# ROwen_main.net
KiCad netlist of a schematic drawn in EAGLE
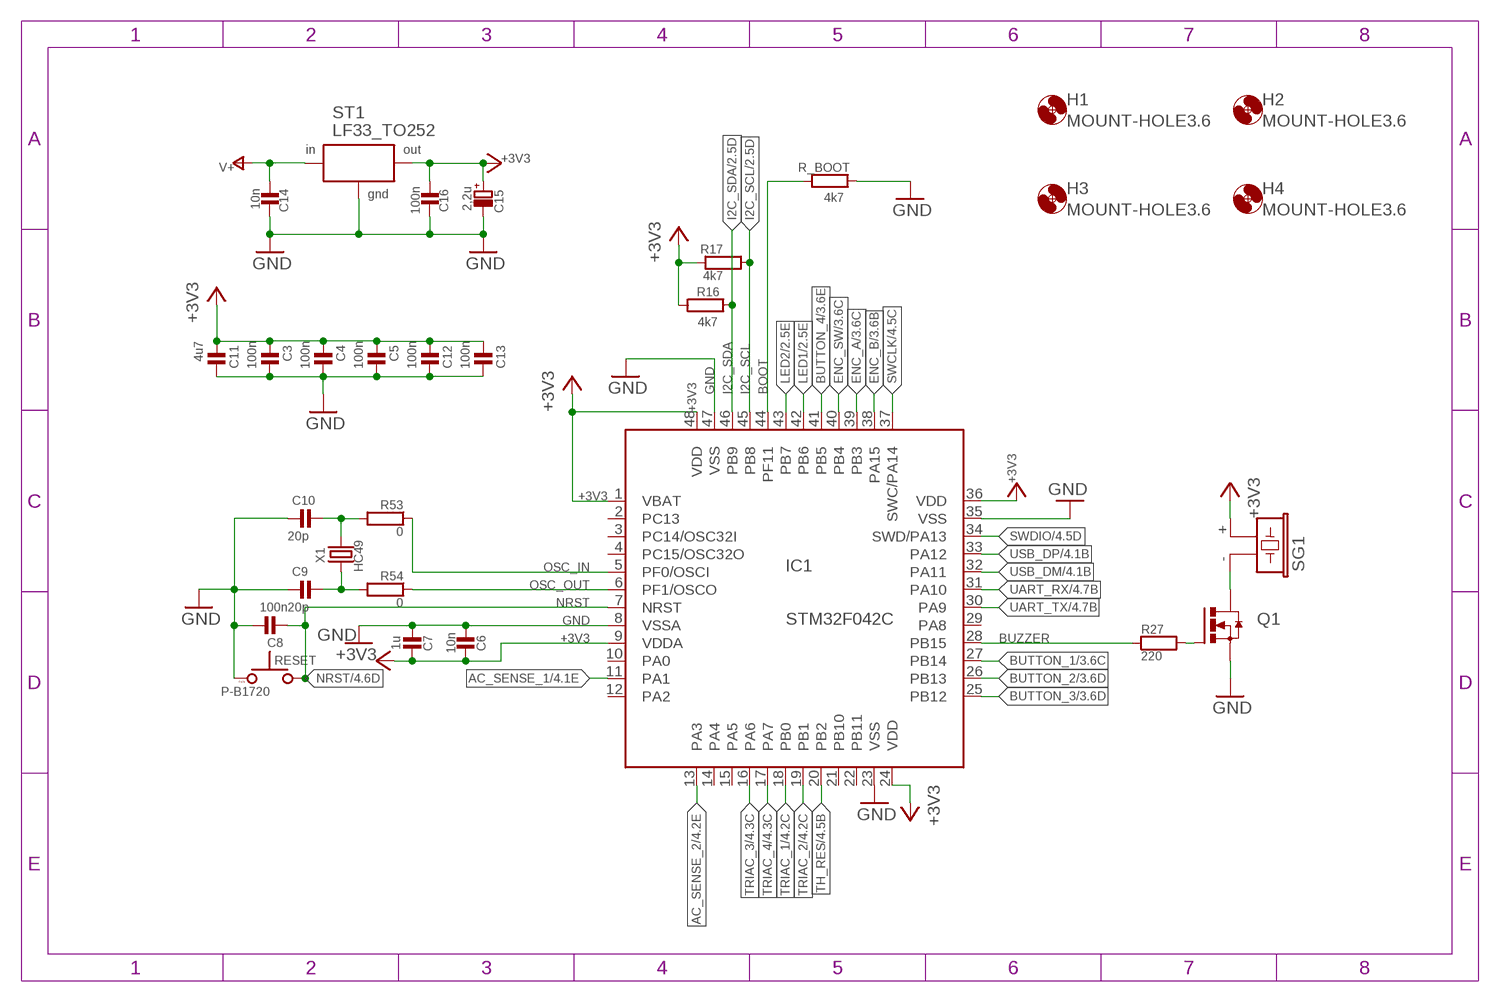
[diagram p0: schematic, sheet 1]
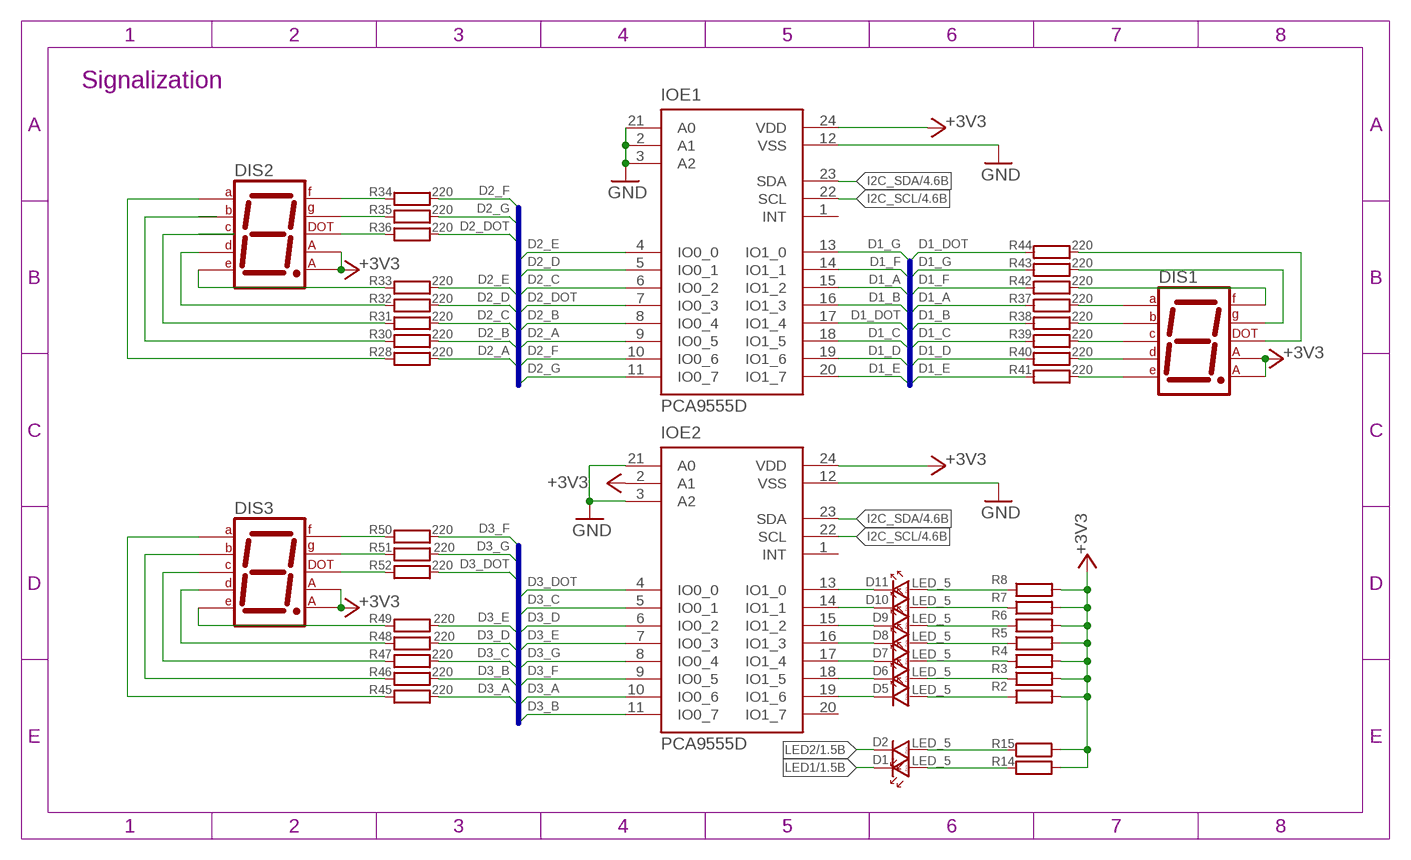
[diagram p1: schematic, sheet 2]
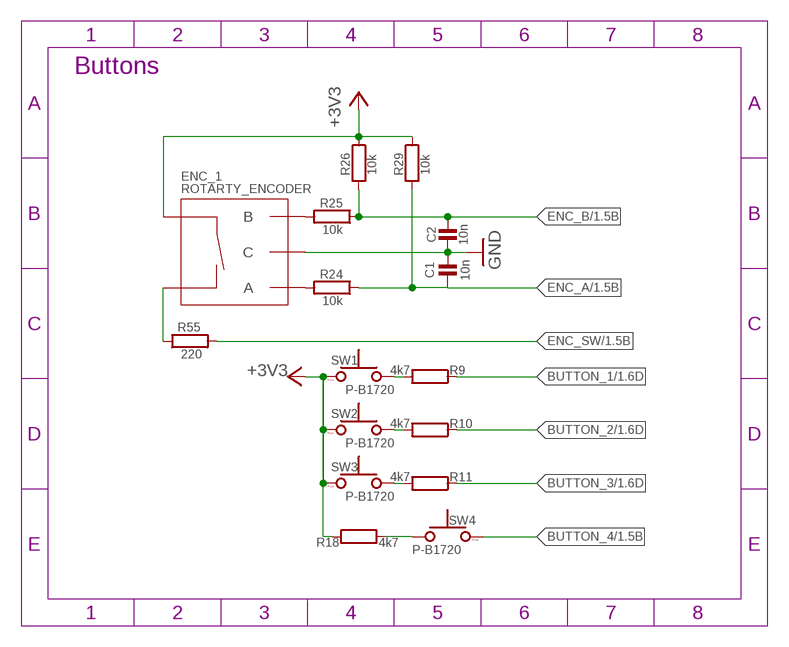
[diagram p2: schematic, sheet 3]
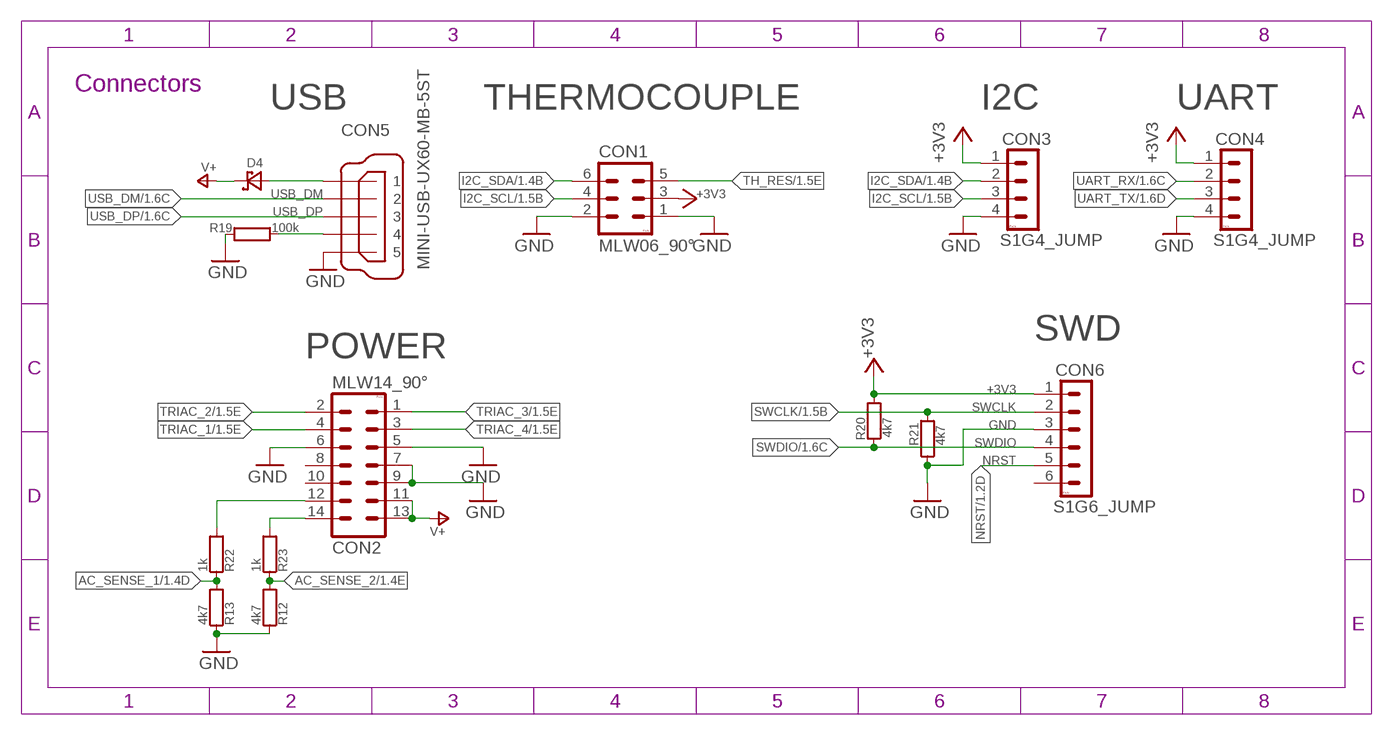
[diagram p3: schematic, sheet 4]

(export (version "E")
  (design (tool "Eeschema 10.0.6"))
  (components
    (comp (ref "C1")
      (value "10n")
      (footprint "eagle-import:0603")
      (libsource (lib "eagle-import") (part "C0603"))
    )
    (comp (ref "C2")
      (value "10n")
      (footprint "eagle-import:0603")
      (libsource (lib "eagle-import") (part "C0603"))
    )
    (comp (ref "ENC_1")
      (value "ROTARTY_ENCODER")
      (footprint "eagle-import:ROTARY_ENC_PLAIN")
      (libsource (lib "eagle-import") (part "ROTARTY_ENCODER"))
    )
    (comp (ref "R9")
      (value "4k7")
      (footprint "eagle-import:0603")
      (libsource (lib "eagle-import") (part "R_R0603"))
    )
    (comp (ref "R10")
      (value "4k7")
      (footprint "eagle-import:0603")
      (libsource (lib "eagle-import") (part "R_R0603"))
    )
    (comp (ref "R11")
      (value "4k7")
      (footprint "eagle-import:0603")
      (libsource (lib "eagle-import") (part "R_R0603"))
    )
    (comp (ref "R18")
      (value "4k7")
      (footprint "eagle-import:0603")
      (libsource (lib "eagle-import") (part "R_R0603"))
    )
    (comp (ref "R24")
      (value "10k")
      (footprint "eagle-import:0603")
      (libsource (lib "eagle-import") (part "R_R0603"))
    )
    (comp (ref "R25")
      (value "10k")
      (footprint "eagle-import:0603")
      (libsource (lib "eagle-import") (part "R_R0603"))
    )
    (comp (ref "R26")
      (value "10k")
      (footprint "eagle-import:0603")
      (libsource (lib "eagle-import") (part "R_R0603"))
    )
    (comp (ref "R29")
      (value "10k")
      (footprint "eagle-import:0603")
      (libsource (lib "eagle-import") (part "R_R0603"))
    )
    (comp (ref "R55")
      (value "220")
      (footprint "eagle-import:0603")
      (libsource (lib "eagle-import") (part "R_R0603"))
    )
    (comp (ref "SW1")
      (value "P-B1720")
      (footprint "eagle-import:P-B1720")
      (libsource (lib "eagle-import") (part "P-B1720"))
    )
    (comp (ref "SW2")
      (value "P-B1720")
      (footprint "eagle-import:P-B1720")
      (libsource (lib "eagle-import") (part "P-B1720"))
    )
    (comp (ref "SW3")
      (value "P-B1720")
      (footprint "eagle-import:P-B1720")
      (libsource (lib "eagle-import") (part "P-B1720"))
    )
    (comp (ref "SW4")
      (value "P-B1720")
      (footprint "eagle-import:P-B1720")
      (libsource (lib "eagle-import") (part "P-B1720"))
    )
    (comp (ref "CON1")
      (value "MLW06_90°")
      (footprint "eagle-import:MLW06A")
      (libsource (lib "eagle-import") (part "MLW06_90°"))
    )
    (comp (ref "CON2")
      (value "MLW14_90°")
      (footprint "eagle-import:MLW14A")
      (libsource (lib "eagle-import") (part "MLW14_90°"))
    )
    (comp (ref "CON3")
      (value "S1G4_JUMP")
      (footprint "eagle-import:S1G4_JUM")
      (libsource (lib "eagle-import") (part "S1G4_JUMP"))
    )
    (comp (ref "CON4")
      (value "S1G4_JUMP")
      (footprint "eagle-import:S1G4_JUM")
      (libsource (lib "eagle-import") (part "S1G4_JUMP"))
    )
    (comp (ref "CON5")
      (value "MINI-USB-UX60-MB-5ST")
      (footprint "eagle-import:UX60-MB-5ST")
      (libsource (lib "eagle-import") (part "MINI-USB-UX60-MB-5ST"))
    )
    (comp (ref "CON6")
      (value "S1G6_JUMP")
      (footprint "eagle-import:S1G6_JUM")
      (libsource (lib "eagle-import") (part "S1G6_JUMP"))
    )
    (comp (ref "D4")
      (value "D_SCHOTKY_SMA")
      (footprint "eagle-import:D_SMA")
      (libsource (lib "eagle-import") (part "D_SCHOTKY_SMA"))
    )
    (comp (ref "R12")
      (value "4k7")
      (footprint "eagle-import:0603")
      (libsource (lib "eagle-import") (part "R_R0603"))
    )
    (comp (ref "R13")
      (value "4k7")
      (footprint "eagle-import:0603")
      (libsource (lib "eagle-import") (part "R_R0603"))
    )
    (comp (ref "R19")
      (value "100k")
      (footprint "eagle-import:0603")
      (libsource (lib "eagle-import") (part "R_R0603"))
    )
    (comp (ref "R20")
      (value "4k7")
      (footprint "eagle-import:0603")
      (libsource (lib "eagle-import") (part "R_R0603"))
    )
    (comp (ref "R21")
      (value "4k7")
      (footprint "eagle-import:0603")
      (libsource (lib "eagle-import") (part "R_R0603"))
    )
    (comp (ref "R22")
      (value "1k")
      (footprint "eagle-import:0603")
      (libsource (lib "eagle-import") (part "R_R0603"))
    )
    (comp (ref "R23")
      (value "1k")
      (footprint "eagle-import:0603")
      (libsource (lib "eagle-import") (part "R_R0603"))
    )
    (comp (ref "C3")
      (value "100n")
      (footprint "eagle-import:0603")
      (libsource (lib "eagle-import") (part "C0603"))
    )
    (comp (ref "C4")
      (value "100n")
      (footprint "eagle-import:0603")
      (libsource (lib "eagle-import") (part "C0603"))
    )
    (comp (ref "C5")
      (value "100n")
      (footprint "eagle-import:0603")
      (libsource (lib "eagle-import") (part "C0603"))
    )
    (comp (ref "C6")
      (value "10n")
      (footprint "eagle-import:0603")
      (libsource (lib "eagle-import") (part "C0603"))
    )
    (comp (ref "C7")
      (value "1u")
      (footprint "eagle-import:0603")
      (libsource (lib "eagle-import") (part "C0603"))
    )
    (comp (ref "C8")
      (value "100n")
      (footprint "eagle-import:0603")
      (libsource (lib "eagle-import") (part "C0603"))
    )
    (comp (ref "C9")
      (value "20p")
      (footprint "eagle-import:0603")
      (libsource (lib "eagle-import") (part "C0603"))
    )
    (comp (ref "C10")
      (value "20p")
      (footprint "eagle-import:0603")
      (libsource (lib "eagle-import") (part "C0603"))
    )
    (comp (ref "C11")
      (value "4u7")
      (footprint "eagle-import:0603")
      (libsource (lib "eagle-import") (part "C0603"))
    )
    (comp (ref "C12")
      (value "100n")
      (footprint "eagle-import:0603")
      (libsource (lib "eagle-import") (part "C0603"))
    )
    (comp (ref "C13")
      (value "100n")
      (footprint "eagle-import:0603")
      (libsource (lib "eagle-import") (part "C0603"))
    )
    (comp (ref "C14")
      (value "10n")
      (footprint "eagle-import:0603")
      (libsource (lib "eagle-import") (part "C0603"))
    )
    (comp (ref "C15")
      (value "2,2u")
      (footprint "eagle-import:ER_08,5_05")
      (libsource (lib "eagle-import") (part "CEE5-8.5"))
    )
    (comp (ref "C16")
      (value "100n")
      (footprint "eagle-import:0603")
      (libsource (lib "eagle-import") (part "C0603"))
    )
    (comp (ref "H1")
      (value "MOUNT-HOLE3.6")
      (footprint "eagle-import:3,6")
      (libsource (lib "eagle-import") (part "MOUNT-HOLE3.6"))
    )
    (comp (ref "H2")
      (value "MOUNT-HOLE3.6")
      (footprint "eagle-import:3,6")
      (libsource (lib "eagle-import") (part "MOUNT-HOLE3.6"))
    )
    (comp (ref "H3")
      (value "MOUNT-HOLE3.6")
      (footprint "eagle-import:3,6")
      (libsource (lib "eagle-import") (part "MOUNT-HOLE3.6"))
    )
    (comp (ref "H4")
      (value "MOUNT-HOLE3.6")
      (footprint "eagle-import:3,6")
      (libsource (lib "eagle-import") (part "MOUNT-HOLE3.6"))
    )
    (comp (ref "IC1")
      (value "STM32F042C")
      (footprint "eagle-import:LQFP48")
      (libsource (lib "eagle-import") (part "STM32F042C"))
    )
    (comp (ref "Q1")
      (value "N-HEXFET-2D_SOT232-IRLL014N")
      (footprint "eagle-import:SOT223")
      (libsource (lib "eagle-import") (part "N-HEXFET-2D_?-SOT232IRLL014N"))
    )
    (comp (ref "R16")
      (value "4k7")
      (footprint "eagle-import:0603")
      (libsource (lib "eagle-import") (part "R_R0603"))
    )
    (comp (ref "R17")
      (value "4k7")
      (footprint "eagle-import:0603")
      (libsource (lib "eagle-import") (part "R_R0603"))
    )
    (comp (ref "R27")
      (value "220")
      (footprint "eagle-import:0603")
      (libsource (lib "eagle-import") (part "R_R0603"))
    )
    (comp (ref "R53")
      (value "0")
      (footprint "eagle-import:0603")
      (libsource (lib "eagle-import") (part "R_R0603"))
    )
    (comp (ref "R54")
      (value "0")
      (footprint "eagle-import:0603")
      (libsource (lib "eagle-import") (part "R_R0603"))
    )
    (comp (ref "RESET")
      (value "P-B1720")
      (footprint "eagle-import:P-B1720")
      (libsource (lib "eagle-import") (part "P-B1720"))
    )
    (comp (ref "R_BOOT")
      (value "4k7")
      (footprint "eagle-import:0603")
      (libsource (lib "eagle-import") (part "R_R0603"))
    )
    (comp (ref "SG1")
      (value "F/CM12P")
      (footprint "eagle-import:F_CM12P")
      (libsource (lib "eagle-import") (part "F/CM12P"))
    )
    (comp (ref "ST1")
      (value "LF33_TO252")
      (footprint "eagle-import:DPACK")
      (fields (field (name "MPN") "LF33CDT-TR"))
      (libsource (lib "eagle-import") (part "LF33_TO252"))
    )
    (comp (ref "X1")
      (value "HC49")
      (footprint "eagle-import:X_HC49_S")
      (libsource (lib "eagle-import") (part "XHC49"))
    )
    (comp (ref "D1")
      (value "LED_5")
      (footprint "eagle-import:LED_5")
      (libsource (lib "eagle-import") (part "LED_5"))
    )
    (comp (ref "D2")
      (value "LED_5")
      (footprint "eagle-import:LED_5")
      (libsource (lib "eagle-import") (part "LED_5"))
    )
    (comp (ref "D5")
      (value "LED_5")
      (footprint "eagle-import:LED_5")
      (libsource (lib "eagle-import") (part "LED_5"))
    )
    (comp (ref "D6")
      (value "LED_5")
      (footprint "eagle-import:LED_5")
      (libsource (lib "eagle-import") (part "LED_5"))
    )
    (comp (ref "D7")
      (value "LED_5")
      (footprint "eagle-import:LED_5")
      (libsource (lib "eagle-import") (part "LED_5"))
    )
    (comp (ref "D8")
      (value "LED_5")
      (footprint "eagle-import:LED_5")
      (libsource (lib "eagle-import") (part "LED_5"))
    )
    (comp (ref "D9")
      (value "LED_5")
      (footprint "eagle-import:LED_5")
      (libsource (lib "eagle-import") (part "LED_5"))
    )
    (comp (ref "D10")
      (value "LED_5")
      (footprint "eagle-import:LED_5")
      (libsource (lib "eagle-import") (part "LED_5"))
    )
    (comp (ref "D11")
      (value "LED_5")
      (footprint "eagle-import:LED_5")
      (libsource (lib "eagle-import") (part "LED_5"))
    )
    (comp (ref "DIS1")
      (value "7-SEGMENT-CA-0.56\"")
      (footprint "eagle-import:7_SEGMENT_0.56_")
      (libsource (lib "eagle-import") (part "7-SEGMENT-CA-0.56{dblquote}"))
    )
    (comp (ref "DIS2")
      (value "7-SEGMENT-CA-0.56\"")
      (footprint "eagle-import:7_SEGMENT_0.56_")
      (libsource (lib "eagle-import") (part "7-SEGMENT-CA-0.56{dblquote}"))
    )
    (comp (ref "DIS3")
      (value "7-SEGMENT-CA-0.56\"")
      (footprint "eagle-import:7_SEGMENT_0.56_")
      (libsource (lib "eagle-import") (part "7-SEGMENT-CA-0.56{dblquote}"))
    )
    (comp (ref "IOE1")
      (value "PCA9555D")
      (footprint "eagle-import:SO24")
      (libsource (lib "eagle-import") (part "PCA9555D"))
    )
    (comp (ref "IOE2")
      (value "PCA9555D")
      (footprint "eagle-import:SO24")
      (libsource (lib "eagle-import") (part "PCA9555D"))
    )
    (comp (ref "R2")
      (value "R_R0603")
      (footprint "eagle-import:0603")
      (libsource (lib "eagle-import") (part "R_R0603"))
    )
    (comp (ref "R3")
      (value "R_R0603")
      (footprint "eagle-import:0603")
      (libsource (lib "eagle-import") (part "R_R0603"))
    )
    (comp (ref "R4")
      (value "R_R0603")
      (footprint "eagle-import:0603")
      (libsource (lib "eagle-import") (part "R_R0603"))
    )
    (comp (ref "R5")
      (value "R_R0603")
      (footprint "eagle-import:0603")
      (libsource (lib "eagle-import") (part "R_R0603"))
    )
    (comp (ref "R6")
      (value "R_R0603")
      (footprint "eagle-import:0603")
      (libsource (lib "eagle-import") (part "R_R0603"))
    )
    (comp (ref "R7")
      (value "R_R0603")
      (footprint "eagle-import:0603")
      (libsource (lib "eagle-import") (part "R_R0603"))
    )
    (comp (ref "R8")
      (value "R_R0603")
      (footprint "eagle-import:0603")
      (libsource (lib "eagle-import") (part "R_R0603"))
    )
    (comp (ref "R14")
      (value "R_R0603")
      (footprint "eagle-import:0603")
      (libsource (lib "eagle-import") (part "R_R0603"))
    )
    (comp (ref "R15")
      (value "R_R0603")
      (footprint "eagle-import:0603")
      (libsource (lib "eagle-import") (part "R_R0603"))
    )
    (comp (ref "R28")
      (value "220")
      (footprint "eagle-import:0603")
      (libsource (lib "eagle-import") (part "R_R0603"))
    )
    (comp (ref "R30")
      (value "220")
      (footprint "eagle-import:0603")
      (libsource (lib "eagle-import") (part "R_R0603"))
    )
    (comp (ref "R31")
      (value "220")
      (footprint "eagle-import:0603")
      (libsource (lib "eagle-import") (part "R_R0603"))
    )
    (comp (ref "R32")
      (value "220")
      (footprint "eagle-import:0603")
      (libsource (lib "eagle-import") (part "R_R0603"))
    )
    (comp (ref "R33")
      (value "220")
      (footprint "eagle-import:0603")
      (libsource (lib "eagle-import") (part "R_R0603"))
    )
    (comp (ref "R34")
      (value "220")
      (footprint "eagle-import:0603")
      (libsource (lib "eagle-import") (part "R_R0603"))
    )
    (comp (ref "R35")
      (value "220")
      (footprint "eagle-import:0603")
      (libsource (lib "eagle-import") (part "R_R0603"))
    )
    (comp (ref "R36")
      (value "220")
      (footprint "eagle-import:0603")
      (libsource (lib "eagle-import") (part "R_R0603"))
    )
    (comp (ref "R37")
      (value "220")
      (footprint "eagle-import:0603")
      (libsource (lib "eagle-import") (part "R_R0603"))
    )
    (comp (ref "R38")
      (value "220")
      (footprint "eagle-import:0603")
      (libsource (lib "eagle-import") (part "R_R0603"))
    )
    (comp (ref "R39")
      (value "220")
      (footprint "eagle-import:0603")
      (libsource (lib "eagle-import") (part "R_R0603"))
    )
    (comp (ref "R40")
      (value "220")
      (footprint "eagle-import:0603")
      (libsource (lib "eagle-import") (part "R_R0603"))
    )
    (comp (ref "R41")
      (value "220")
      (footprint "eagle-import:0603")
      (libsource (lib "eagle-import") (part "R_R0603"))
    )
    (comp (ref "R42")
      (value "220")
      (footprint "eagle-import:0603")
      (libsource (lib "eagle-import") (part "R_R0603"))
    )
    (comp (ref "R43")
      (value "220")
      (footprint "eagle-import:0603")
      (libsource (lib "eagle-import") (part "R_R0603"))
    )
    (comp (ref "R44")
      (value "220")
      (footprint "eagle-import:0603")
      (libsource (lib "eagle-import") (part "R_R0603"))
    )
    (comp (ref "R45")
      (value "220")
      (footprint "eagle-import:0603")
      (libsource (lib "eagle-import") (part "R_R0603"))
    )
    (comp (ref "R46")
      (value "220")
      (footprint "eagle-import:0603")
      (libsource (lib "eagle-import") (part "R_R0603"))
    )
    (comp (ref "R47")
      (value "220")
      (footprint "eagle-import:0603")
      (libsource (lib "eagle-import") (part "R_R0603"))
    )
    (comp (ref "R48")
      (value "220")
      (footprint "eagle-import:0603")
      (libsource (lib "eagle-import") (part "R_R0603"))
    )
    (comp (ref "R49")
      (value "220")
      (footprint "eagle-import:0603")
      (libsource (lib "eagle-import") (part "R_R0603"))
    )
    (comp (ref "R50")
      (value "220")
      (footprint "eagle-import:0603")
      (libsource (lib "eagle-import") (part "R_R0603"))
    )
    (comp (ref "R51")
      (value "220")
      (footprint "eagle-import:0603")
      (libsource (lib "eagle-import") (part "R_R0603"))
    )
    (comp (ref "R52")
      (value "220")
      (footprint "eagle-import:0603")
      (libsource (lib "eagle-import") (part "R_R0603"))
    )
  )
  (nets
    (net (code "1") (name "+3V3") (class "Default")
      (node (ref "C11") (pin "2") (pinfunction "2_2") (pintype "passive"))
      (node (ref "C12") (pin "2") (pinfunction "2_2") (pintype "passive"))
      (node (ref "C13") (pin "2") (pinfunction "2_2") (pintype "passive"))
      (node (ref "C15") (pin "+") (pinfunction "+_+") (pintype "passive"))
      (node (ref "C16") (pin "2") (pinfunction "2_2") (pintype "passive"))
      (node (ref "C3") (pin "2") (pinfunction "2_2") (pintype "passive"))
      (node (ref "C4") (pin "2") (pinfunction "2_2") (pintype "passive"))
      (node (ref "C5") (pin "2") (pinfunction "2_2") (pintype "passive"))
      (node (ref "C6") (pin "1") (pinfunction "1_1") (pintype "passive"))
      (node (ref "C7") (pin "1") (pinfunction "1_1") (pintype "passive"))
      (node (ref "CON1") (pin "3") (pinfunction "3_3") (pintype "passive"))
      (node (ref "CON3") (pin "1") (pinfunction "1_1") (pintype "passive"))
      (node (ref "CON4") (pin "1") (pinfunction "1_1") (pintype "passive"))
      (node (ref "CON6") (pin "1") (pinfunction "1_1") (pintype "passive"))
      (node (ref "DIS1") (pin "3") (pinfunction "CA2_3") (pintype "passive"))
      (node (ref "DIS1") (pin "8") (pinfunction "CA1_8") (pintype "passive"))
      (node (ref "DIS2") (pin "3") (pinfunction "CA2_3") (pintype "passive"))
      (node (ref "DIS2") (pin "8") (pinfunction "CA1_8") (pintype "passive"))
      (node (ref "DIS3") (pin "3") (pinfunction "CA2_3") (pintype "passive"))
      (node (ref "DIS3") (pin "8") (pinfunction "CA1_8") (pintype "passive"))
      (node (ref "ENC_1") (pin "SW+") (pinfunction "SW+_SW+") (pintype "bidirectional"))
      (node (ref "IC1") (pin "1") (pinfunction "VBAT_1") (pintype "passive"))
      (node (ref "IC1") (pin "24") (pinfunction "VDD_24") (pintype "passive"))
      (node (ref "IC1") (pin "36") (pinfunction "VDD_36") (pintype "passive"))
      (node (ref "IC1") (pin "48") (pinfunction "VDD_48") (pintype "passive"))
      (node (ref "IC1") (pin "9") (pinfunction "VDDA_9") (pintype "passive"))
      (node (ref "IOE1") (pin "24") (pinfunction "VDD_24") (pintype "passive"))
      (node (ref "IOE2") (pin "2") (pinfunction "A1_2") (pintype "bidirectional"))
      (node (ref "IOE2") (pin "24") (pinfunction "VDD_24") (pintype "passive"))
      (node (ref "R14") (pin "2") (pinfunction "2_2") (pintype "passive"))
      (node (ref "R15") (pin "2") (pinfunction "2_2") (pintype "passive"))
      (node (ref "R16") (pin "2") (pinfunction "2_2") (pintype "passive"))
      (node (ref "R17") (pin "2") (pinfunction "2_2") (pintype "passive"))
      (node (ref "R18") (pin "1") (pinfunction "1_1") (pintype "passive"))
      (node (ref "R2") (pin "2") (pinfunction "2_2") (pintype "passive"))
      (node (ref "R20") (pin "2") (pinfunction "2_2") (pintype "passive"))
      (node (ref "R26") (pin "1") (pinfunction "1_1") (pintype "passive"))
      (node (ref "R29") (pin "1") (pinfunction "1_1") (pintype "passive"))
      (node (ref "R3") (pin "2") (pinfunction "2_2") (pintype "passive"))
      (node (ref "R4") (pin "2") (pinfunction "2_2") (pintype "passive"))
      (node (ref "R5") (pin "2") (pinfunction "2_2") (pintype "passive"))
      (node (ref "R6") (pin "2") (pinfunction "2_2") (pintype "passive"))
      (node (ref "R7") (pin "2") (pinfunction "2_2") (pintype "passive"))
      (node (ref "R8") (pin "2") (pinfunction "2_2") (pintype "passive"))
      (node (ref "SG1") (pin "+") (pinfunction "1_+") (pintype "passive"))
      (node (ref "ST1") (pin "3") (pinfunction "OUT_3") (pintype "bidirectional"))
      (node (ref "SW1") (pin "1") (pinfunction "1_1") (pintype "passive"))
      (node (ref "SW2") (pin "1") (pinfunction "1_1") (pintype "passive"))
      (node (ref "SW3") (pin "1") (pinfunction "1_1") (pintype "passive"))
    )
    (net (code "2") (name "AC_SENSE_1") (class "Default")
      (node (ref "IC1") (pin "11") (pinfunction "PA1_11") (pintype "passive"))
      (node (ref "R13") (pin "2") (pinfunction "2_2") (pintype "passive"))
      (node (ref "R22") (pin "1") (pinfunction "1_1") (pintype "passive"))
    )
    (net (code "3") (name "AC_SENSE_2") (class "Default")
      (node (ref "IC1") (pin "13") (pinfunction "PA3_13") (pintype "passive"))
      (node (ref "R12") (pin "2") (pinfunction "2_2") (pintype "passive"))
      (node (ref "R23") (pin "1") (pinfunction "1_1") (pintype "passive"))
    )
    (net (code "4") (name "BOOT") (class "Default")
      (node (ref "IC1") (pin "44") (pinfunction "PF11_44") (pintype "passive"))
      (node (ref "R_BOOT") (pin "2") (pinfunction "2_2") (pintype "passive"))
    )
    (net (code "5") (name "BUTTON_1") (class "Default")
      (node (ref "IC1") (pin "27") (pinfunction "PB14_27") (pintype "passive"))
      (node (ref "R9") (pin "1") (pinfunction "1_1") (pintype "passive"))
    )
    (net (code "6") (name "BUTTON_2") (class "Default")
      (node (ref "IC1") (pin "26") (pinfunction "PB13_26") (pintype "passive"))
      (node (ref "R10") (pin "1") (pinfunction "1_1") (pintype "passive"))
    )
    (net (code "7") (name "BUTTON_3") (class "Default")
      (node (ref "IC1") (pin "25") (pinfunction "PB12_25") (pintype "passive"))
      (node (ref "R11") (pin "1") (pinfunction "1_1") (pintype "passive"))
    )
    (net (code "8") (name "BUTTON_4") (class "Default")
      (node (ref "IC1") (pin "41") (pinfunction "PB5_41") (pintype "passive"))
      (node (ref "SW4") (pin "1") (pinfunction "1_1") (pintype "passive"))
    )
    (net (code "9") (name "BUZZER") (class "Default")
      (node (ref "IC1") (pin "28") (pinfunction "PB15_28") (pintype "passive"))
      (node (ref "R27") (pin "1") (pinfunction "1_1") (pintype "passive"))
    )
    (net (code "10") (name "D1_A") (class "Default")
      (node (ref "IOE1") (pin "15") (pinfunction "IO1_2_15") (pintype "bidirectional"))
      (node (ref "R37") (pin "2") (pinfunction "2_2") (pintype "passive"))
    )
    (net (code "11") (name "D1_B") (class "Default")
      (node (ref "IOE1") (pin "16") (pinfunction "IO1_3_16") (pintype "bidirectional"))
      (node (ref "R38") (pin "2") (pinfunction "2_2") (pintype "passive"))
    )
    (net (code "12") (name "D1_C") (class "Default")
      (node (ref "IOE1") (pin "18") (pinfunction "IO1_5_18") (pintype "bidirectional"))
      (node (ref "R39") (pin "2") (pinfunction "2_2") (pintype "passive"))
    )
    (net (code "13") (name "D1_D") (class "Default")
      (node (ref "IOE1") (pin "19") (pinfunction "IO1_6_19") (pintype "bidirectional"))
      (node (ref "R40") (pin "2") (pinfunction "2_2") (pintype "passive"))
    )
    (net (code "14") (name "D1_DOT") (class "Default")
      (node (ref "IOE1") (pin "17") (pinfunction "IO1_4_17") (pintype "bidirectional"))
      (node (ref "R44") (pin "2") (pinfunction "2_2") (pintype "passive"))
    )
    (net (code "15") (name "D1_E") (class "Default")
      (node (ref "IOE1") (pin "20") (pinfunction "IO1_7_20") (pintype "bidirectional"))
      (node (ref "R41") (pin "2") (pinfunction "2_2") (pintype "passive"))
    )
    (net (code "16") (name "D1_F") (class "Default")
      (node (ref "IOE1") (pin "14") (pinfunction "IO1_1_14") (pintype "bidirectional"))
      (node (ref "R42") (pin "2") (pinfunction "2_2") (pintype "passive"))
    )
    (net (code "17") (name "D1_G") (class "Default")
      (node (ref "IOE1") (pin "13") (pinfunction "IO1_0_13") (pintype "bidirectional"))
      (node (ref "R43") (pin "2") (pinfunction "2_2") (pintype "passive"))
    )
    (net (code "18") (name "D2_A") (class "Default")
      (node (ref "IOE1") (pin "9") (pinfunction "IO0_5_9") (pintype "bidirectional"))
      (node (ref "R28") (pin "2") (pinfunction "2_2") (pintype "passive"))
    )
    (net (code "19") (name "D2_B") (class "Default")
      (node (ref "IOE1") (pin "8") (pinfunction "IO0_4_8") (pintype "bidirectional"))
      (node (ref "R30") (pin "2") (pinfunction "2_2") (pintype "passive"))
    )
    (net (code "20") (name "D2_C") (class "Default")
      (node (ref "IOE1") (pin "6") (pinfunction "IO0_2_6") (pintype "bidirectional"))
      (node (ref "R31") (pin "2") (pinfunction "2_2") (pintype "passive"))
    )
    (net (code "21") (name "D2_D") (class "Default")
      (node (ref "IOE1") (pin "5") (pinfunction "IO0_1_5") (pintype "bidirectional"))
      (node (ref "R32") (pin "2") (pinfunction "2_2") (pintype "passive"))
    )
    (net (code "22") (name "D2_DOT") (class "Default")
      (node (ref "IOE1") (pin "7") (pinfunction "IO0_3_7") (pintype "bidirectional"))
      (node (ref "R36") (pin "2") (pinfunction "2_2") (pintype "passive"))
    )
    (net (code "23") (name "D2_E") (class "Default")
      (node (ref "IOE1") (pin "4") (pinfunction "IO0_0_4") (pintype "bidirectional"))
      (node (ref "R33") (pin "2") (pinfunction "2_2") (pintype "passive"))
    )
    (net (code "24") (name "D2_F") (class "Default")
      (node (ref "IOE1") (pin "10") (pinfunction "IO0_6_10") (pintype "bidirectional"))
      (node (ref "R34") (pin "2") (pinfunction "2_2") (pintype "passive"))
    )
    (net (code "25") (name "D2_G") (class "Default")
      (node (ref "IOE1") (pin "11") (pinfunction "IO0_7_11") (pintype "bidirectional"))
      (node (ref "R35") (pin "2") (pinfunction "2_2") (pintype "passive"))
    )
    (net (code "26") (name "D3_A") (class "Default")
      (node (ref "IOE2") (pin "10") (pinfunction "IO0_6_10") (pintype "bidirectional"))
      (node (ref "R45") (pin "2") (pinfunction "2_2") (pintype "passive"))
    )
    (net (code "27") (name "D3_B") (class "Default")
      (node (ref "IOE2") (pin "11") (pinfunction "IO0_7_11") (pintype "bidirectional"))
      (node (ref "R46") (pin "2") (pinfunction "2_2") (pintype "passive"))
    )
    (net (code "28") (name "D3_C") (class "Default")
      (node (ref "IOE2") (pin "5") (pinfunction "IO0_1_5") (pintype "bidirectional"))
      (node (ref "R47") (pin "2") (pinfunction "2_2") (pintype "passive"))
    )
    (net (code "29") (name "D3_D") (class "Default")
      (node (ref "IOE2") (pin "6") (pinfunction "IO0_2_6") (pintype "bidirectional"))
      (node (ref "R48") (pin "2") (pinfunction "2_2") (pintype "passive"))
    )
    (net (code "30") (name "D3_DOT") (class "Default")
      (node (ref "IOE2") (pin "4") (pinfunction "IO0_0_4") (pintype "bidirectional"))
      (node (ref "R52") (pin "2") (pinfunction "2_2") (pintype "passive"))
    )
    (net (code "31") (name "D3_E") (class "Default")
      (node (ref "IOE2") (pin "7") (pinfunction "IO0_3_7") (pintype "bidirectional"))
      (node (ref "R49") (pin "2") (pinfunction "2_2") (pintype "passive"))
    )
    (net (code "32") (name "D3_F") (class "Default")
      (node (ref "IOE2") (pin "9") (pinfunction "IO0_5_9") (pintype "bidirectional"))
      (node (ref "R50") (pin "2") (pinfunction "2_2") (pintype "passive"))
    )
    (net (code "33") (name "D3_G") (class "Default")
      (node (ref "IOE2") (pin "8") (pinfunction "IO0_4_8") (pintype "bidirectional"))
      (node (ref "R51") (pin "2") (pinfunction "2_2") (pintype "passive"))
    )
    (net (code "34") (name "ENC_A") (class "Default")
      (node (ref "C1") (pin "2") (pinfunction "2_2") (pintype "passive"))
      (node (ref "IC1") (pin "39") (pinfunction "PB3_39") (pintype "passive"))
      (node (ref "R24") (pin "1") (pinfunction "1_1") (pintype "passive"))
      (node (ref "R29") (pin "2") (pinfunction "2_2") (pintype "passive"))
    )
    (net (code "35") (name "ENC_B") (class "Default")
      (node (ref "C2") (pin "1") (pinfunction "1_1") (pintype "passive"))
      (node (ref "IC1") (pin "38") (pinfunction "PA15_38") (pintype "passive"))
      (node (ref "R25") (pin "1") (pinfunction "1_1") (pintype "passive"))
      (node (ref "R26") (pin "2") (pinfunction "2_2") (pintype "passive"))
    )
    (net (code "36") (name "ENC_SW") (class "Default")
      (node (ref "IC1") (pin "40") (pinfunction "PB4_40") (pintype "passive"))
      (node (ref "R55") (pin "2") (pinfunction "2_2") (pintype "passive"))
    )
    (net (code "37") (name "GND") (class "Default")
      (node (ref "C1") (pin "1") (pinfunction "1_1") (pintype "passive"))
      (node (ref "C10") (pin "2") (pinfunction "2_2") (pintype "passive"))
      (node (ref "C11") (pin "1") (pinfunction "1_1") (pintype "passive"))
      (node (ref "C12") (pin "1") (pinfunction "1_1") (pintype "passive"))
      (node (ref "C13") (pin "1") (pinfunction "1_1") (pintype "passive"))
      (node (ref "C14") (pin "2") (pinfunction "2_2") (pintype "passive"))
      (node (ref "C15") (pin "-") (pinfunction "-_-") (pintype "passive"))
      (node (ref "C16") (pin "1") (pinfunction "1_1") (pintype "passive"))
      (node (ref "C2") (pin "2") (pinfunction "2_2") (pintype "passive"))
      (node (ref "C3") (pin "1") (pinfunction "1_1") (pintype "passive"))
      (node (ref "C4") (pin "1") (pinfunction "1_1") (pintype "passive"))
      (node (ref "C5") (pin "1") (pinfunction "1_1") (pintype "passive"))
      (node (ref "C6") (pin "2") (pinfunction "2_2") (pintype "passive"))
      (node (ref "C7") (pin "2") (pinfunction "2_2") (pintype "passive"))
      (node (ref "C8") (pin "1") (pinfunction "1_1") (pintype "passive"))
      (node (ref "C9") (pin "2") (pinfunction "2_2") (pintype "passive"))
      (node (ref "CON1") (pin "1") (pinfunction "1_1") (pintype "passive"))
      (node (ref "CON1") (pin "2") (pinfunction "2_2") (pintype "passive"))
      (node (ref "CON2") (pin "5") (pinfunction "5_5") (pintype "passive"))
      (node (ref "CON2") (pin "6") (pinfunction "6_6") (pintype "passive"))
      (node (ref "CON2") (pin "7") (pinfunction "7_7") (pintype "passive"))
      (node (ref "CON2") (pin "9") (pinfunction "9_9") (pintype "passive"))
      (node (ref "CON3") (pin "4") (pinfunction "4_4") (pintype "passive"))
      (node (ref "CON4") (pin "4") (pinfunction "4_4") (pintype "passive"))
      (node (ref "CON5") (pin "5") (pinfunction "5_5") (pintype "input"))
      (node (ref "CON6") (pin "3") (pinfunction "3_3") (pintype "passive"))
      (node (ref "ENC_1") (pin "C") (pinfunction "C_C") (pintype "bidirectional"))
      (node (ref "IC1") (pin "23") (pinfunction "VSS_23") (pintype "passive"))
      (node (ref "IC1") (pin "35") (pinfunction "VSS_35") (pintype "passive"))
      (node (ref "IC1") (pin "47") (pinfunction "VSS_47") (pintype "passive"))
      (node (ref "IC1") (pin "8") (pinfunction "VSSA_8") (pintype "passive"))
      (node (ref "IOE1") (pin "12") (pinfunction "VSS_12") (pintype "passive"))
      (node (ref "IOE1") (pin "2") (pinfunction "A1_2") (pintype "bidirectional"))
      (node (ref "IOE1") (pin "21") (pinfunction "A0_21") (pintype "bidirectional"))
      (node (ref "IOE1") (pin "3") (pinfunction "A2_3") (pintype "bidirectional"))
      (node (ref "IOE2") (pin "12") (pinfunction "VSS_12") (pintype "passive"))
      (node (ref "IOE2") (pin "21") (pinfunction "A0_21") (pintype "bidirectional"))
      (node (ref "IOE2") (pin "3") (pinfunction "A2_3") (pintype "bidirectional"))
      (node (ref "Q1") (pin "3") (pinfunction "S_3") (pintype "passive"))
      (node (ref "R12") (pin "1") (pinfunction "1_1") (pintype "passive"))
      (node (ref "R13") (pin "1") (pinfunction "1_1") (pintype "passive"))
      (node (ref "R19") (pin "1") (pinfunction "1_1") (pintype "passive"))
      (node (ref "R21") (pin "1") (pinfunction "1_1") (pintype "passive"))
      (node (ref "RESET") (pin "1") (pinfunction "1_1") (pintype "passive"))
      (node (ref "R_BOOT") (pin "1") (pinfunction "1_1") (pintype "passive"))
      (node (ref "ST1") (pin "2") (pinfunction "GND_2") (pintype "bidirectional"))
    )
    (net (code "38") (name "I2C_SCL") (class "Default")
      (node (ref "CON1") (pin "4") (pinfunction "4_4") (pintype "passive"))
      (node (ref "CON3") (pin "3") (pinfunction "3_3") (pintype "passive"))
      (node (ref "IC1") (pin "45") (pinfunction "PB8_45") (pintype "passive"))
      (node (ref "IOE1") (pin "22") (pinfunction "SCL_22") (pintype "bidirectional"))
      (node (ref "IOE2") (pin "22") (pinfunction "SCL_22") (pintype "bidirectional"))
      (node (ref "R17") (pin "1") (pinfunction "1_1") (pintype "passive"))
    )
    (net (code "39") (name "I2C_SDA") (class "Default")
      (node (ref "CON1") (pin "6") (pinfunction "6_6") (pintype "passive"))
      (node (ref "CON3") (pin "2") (pinfunction "2_2") (pintype "passive"))
      (node (ref "IC1") (pin "46") (pinfunction "PB9_46") (pintype "passive"))
      (node (ref "IOE1") (pin "23") (pinfunction "SDA_23") (pintype "bidirectional"))
      (node (ref "IOE2") (pin "23") (pinfunction "SDA_23") (pintype "bidirectional"))
      (node (ref "R16") (pin "1") (pinfunction "1_1") (pintype "passive"))
    )
    (net (code "40") (name "LED1") (class "Default")
      (node (ref "D1") (pin "K") (pinfunction "K_K") (pintype "passive"))
      (node (ref "IC1") (pin "42") (pinfunction "PB6_42") (pintype "passive"))
    )
    (net (code "41") (name "LED2") (class "Default")
      (node (ref "D2") (pin "K") (pinfunction "K_K") (pintype "passive"))
      (node (ref "IC1") (pin "43") (pinfunction "PB7_43") (pintype "passive"))
    )
    (net (code "42") (name "NRST") (class "Default")
      (node (ref "C8") (pin "2") (pinfunction "2_2") (pintype "passive"))
      (node (ref "CON6") (pin "5") (pinfunction "5_5") (pintype "passive"))
      (node (ref "IC1") (pin "7") (pinfunction "NRST_7") (pintype "passive"))
      (node (ref "RESET") (pin "2") (pinfunction "2_2") (pintype "passive"))
    )
    (net (code "43") (name "Net-(C9-Pad1)") (class "Default")
      (node (ref "C9") (pin "1") (pinfunction "1_1") (pintype "passive"))
      (node (ref "R54") (pin "2") (pinfunction "2_2") (pintype "passive"))
      (node (ref "X1") (pin "1") (pinfunction "1_1") (pintype "passive"))
    )
    (net (code "44") (name "Net-(C10-Pad1)") (class "Default")
      (node (ref "C10") (pin "1") (pinfunction "1_1") (pintype "passive"))
      (node (ref "R53") (pin "2") (pinfunction "2_2") (pintype "passive"))
      (node (ref "X1") (pin "2") (pinfunction "2_2") (pintype "passive"))
    )
    (net (code "45") (name "Net-(CON2-Pad12)") (class "Default")
      (node (ref "CON2") (pin "12") (pinfunction "12_12") (pintype "passive"))
      (node (ref "R22") (pin "2") (pinfunction "2_2") (pintype "passive"))
    )
    (net (code "46") (name "Net-(CON2-Pad14)") (class "Default")
      (node (ref "CON2") (pin "14") (pinfunction "14_14") (pintype "passive"))
      (node (ref "R23") (pin "2") (pinfunction "2_2") (pintype "passive"))
    )
    (net (code "47") (name "Net-(CON5-Pad1)") (class "Default")
      (node (ref "CON5") (pin "1") (pinfunction "1_1") (pintype "input"))
      (node (ref "D4") (pin "A") (pinfunction "A_A") (pintype "passive"))
    )
    (net (code "48") (name "Net-(CON5-Pad4)") (class "Default")
      (node (ref "CON5") (pin "4") (pinfunction "4_4") (pintype "input"))
      (node (ref "R19") (pin "2") (pinfunction "2_2") (pintype "passive"))
    )
    (net (code "49") (name "Net-(D1-PadA)") (class "Default")
      (node (ref "D1") (pin "A") (pinfunction "A_A") (pintype "passive"))
      (node (ref "R14") (pin "1") (pinfunction "1_1") (pintype "passive"))
    )
    (net (code "50") (name "Net-(D2-PadA)") (class "Default")
      (node (ref "D2") (pin "A") (pinfunction "A_A") (pintype "passive"))
      (node (ref "R15") (pin "1") (pinfunction "1_1") (pintype "passive"))
    )
    (net (code "51") (name "Net-(D5-PadA)") (class "Default")
      (node (ref "D5") (pin "A") (pinfunction "A_A") (pintype "passive"))
      (node (ref "R2") (pin "1") (pinfunction "1_1") (pintype "passive"))
    )
    (net (code "52") (name "Net-(D6-PadA)") (class "Default")
      (node (ref "D6") (pin "A") (pinfunction "A_A") (pintype "passive"))
      (node (ref "R3") (pin "1") (pinfunction "1_1") (pintype "passive"))
    )
    (net (code "53") (name "Net-(D7-PadA)") (class "Default")
      (node (ref "D7") (pin "A") (pinfunction "A_A") (pintype "passive"))
      (node (ref "R4") (pin "1") (pinfunction "1_1") (pintype "passive"))
    )
    (net (code "54") (name "Net-(D8-PadA)") (class "Default")
      (node (ref "D8") (pin "A") (pinfunction "A_A") (pintype "passive"))
      (node (ref "R5") (pin "1") (pinfunction "1_1") (pintype "passive"))
    )
    (net (code "55") (name "Net-(D9-PadA)") (class "Default")
      (node (ref "D9") (pin "A") (pinfunction "A_A") (pintype "passive"))
      (node (ref "R6") (pin "1") (pinfunction "1_1") (pintype "passive"))
    )
    (net (code "56") (name "Net-(D10-PadA)") (class "Default")
      (node (ref "D10") (pin "A") (pinfunction "A_A") (pintype "passive"))
      (node (ref "R7") (pin "1") (pinfunction "1_1") (pintype "passive"))
    )
    (net (code "57") (name "Net-(D11-PadA)") (class "Default")
      (node (ref "D11") (pin "A") (pinfunction "A_A") (pintype "passive"))
      (node (ref "R8") (pin "1") (pinfunction "1_1") (pintype "passive"))
    )
    (net (code "58") (name "Net-(DIS1-A)") (class "Default")
      (node (ref "DIS1") (pin "7") (pinfunction "A_7") (pintype "passive"))
      (node (ref "R37") (pin "1") (pinfunction "1_1") (pintype "passive"))
    )
    (net (code "59") (name "Net-(DIS1-B)") (class "Default")
      (node (ref "DIS1") (pin "6") (pinfunction "B_6") (pintype "passive"))
      (node (ref "R38") (pin "1") (pinfunction "1_1") (pintype "passive"))
    )
    (net (code "60") (name "Net-(DIS1-C)") (class "Default")
      (node (ref "DIS1") (pin "4") (pinfunction "C_4") (pintype "passive"))
      (node (ref "R39") (pin "1") (pinfunction "1_1") (pintype "passive"))
    )
    (net (code "61") (name "Net-(DIS1-D)") (class "Default")
      (node (ref "DIS1") (pin "2") (pinfunction "D_2") (pintype "passive"))
      (node (ref "R40") (pin "1") (pinfunction "1_1") (pintype "passive"))
    )
    (net (code "62") (name "Net-(DIS1-DP)") (class "Default")
      (node (ref "DIS1") (pin "5") (pinfunction "DP_5") (pintype "passive"))
      (node (ref "R44") (pin "1") (pinfunction "1_1") (pintype "passive"))
    )
    (net (code "63") (name "Net-(DIS1-E)") (class "Default")
      (node (ref "DIS1") (pin "1") (pinfunction "E_1") (pintype "passive"))
      (node (ref "R41") (pin "1") (pinfunction "1_1") (pintype "passive"))
    )
    (net (code "64") (name "Net-(DIS1-F)") (class "Default")
      (node (ref "DIS1") (pin "9") (pinfunction "F_9") (pintype "passive"))
      (node (ref "R42") (pin "1") (pinfunction "1_1") (pintype "passive"))
    )
    (net (code "65") (name "Net-(DIS1-G)") (class "Default")
      (node (ref "DIS1") (pin "10") (pinfunction "G_10") (pintype "passive"))
      (node (ref "R43") (pin "1") (pinfunction "1_1") (pintype "passive"))
    )
    (net (code "66") (name "Net-(DIS2-A)") (class "Default")
      (node (ref "DIS2") (pin "7") (pinfunction "A_7") (pintype "passive"))
      (node (ref "R28") (pin "1") (pinfunction "1_1") (pintype "passive"))
    )
    (net (code "67") (name "Net-(DIS2-B)") (class "Default")
      (node (ref "DIS2") (pin "6") (pinfunction "B_6") (pintype "passive"))
      (node (ref "R30") (pin "1") (pinfunction "1_1") (pintype "passive"))
    )
    (net (code "68") (name "Net-(DIS2-C)") (class "Default")
      (node (ref "DIS2") (pin "4") (pinfunction "C_4") (pintype "passive"))
      (node (ref "R31") (pin "1") (pinfunction "1_1") (pintype "passive"))
    )
    (net (code "69") (name "Net-(DIS2-D)") (class "Default")
      (node (ref "DIS2") (pin "2") (pinfunction "D_2") (pintype "passive"))
      (node (ref "R32") (pin "1") (pinfunction "1_1") (pintype "passive"))
    )
    (net (code "70") (name "Net-(DIS2-DP)") (class "Default")
      (node (ref "DIS2") (pin "5") (pinfunction "DP_5") (pintype "passive"))
      (node (ref "R36") (pin "1") (pinfunction "1_1") (pintype "passive"))
    )
    (net (code "71") (name "Net-(DIS2-E)") (class "Default")
      (node (ref "DIS2") (pin "1") (pinfunction "E_1") (pintype "passive"))
      (node (ref "R33") (pin "1") (pinfunction "1_1") (pintype "passive"))
    )
    (net (code "72") (name "Net-(DIS2-F)") (class "Default")
      (node (ref "DIS2") (pin "9") (pinfunction "F_9") (pintype "passive"))
      (node (ref "R34") (pin "1") (pinfunction "1_1") (pintype "passive"))
    )
    (net (code "73") (name "Net-(DIS2-G)") (class "Default")
      (node (ref "DIS2") (pin "10") (pinfunction "G_10") (pintype "passive"))
      (node (ref "R35") (pin "1") (pinfunction "1_1") (pintype "passive"))
    )
    (net (code "74") (name "Net-(DIS3-A)") (class "Default")
      (node (ref "DIS3") (pin "7") (pinfunction "A_7") (pintype "passive"))
      (node (ref "R45") (pin "1") (pinfunction "1_1") (pintype "passive"))
    )
    (net (code "75") (name "Net-(DIS3-B)") (class "Default")
      (node (ref "DIS3") (pin "6") (pinfunction "B_6") (pintype "passive"))
      (node (ref "R46") (pin "1") (pinfunction "1_1") (pintype "passive"))
    )
    (net (code "76") (name "Net-(DIS3-C)") (class "Default")
      (node (ref "DIS3") (pin "4") (pinfunction "C_4") (pintype "passive"))
      (node (ref "R47") (pin "1") (pinfunction "1_1") (pintype "passive"))
    )
    (net (code "77") (name "Net-(DIS3-D)") (class "Default")
      (node (ref "DIS3") (pin "2") (pinfunction "D_2") (pintype "passive"))
      (node (ref "R48") (pin "1") (pinfunction "1_1") (pintype "passive"))
    )
    (net (code "78") (name "Net-(DIS3-DP)") (class "Default")
      (node (ref "DIS3") (pin "5") (pinfunction "DP_5") (pintype "passive"))
      (node (ref "R52") (pin "1") (pinfunction "1_1") (pintype "passive"))
    )
    (net (code "79") (name "Net-(DIS3-E)") (class "Default")
      (node (ref "DIS3") (pin "1") (pinfunction "E_1") (pintype "passive"))
      (node (ref "R49") (pin "1") (pinfunction "1_1") (pintype "passive"))
    )
    (net (code "80") (name "Net-(DIS3-F)") (class "Default")
      (node (ref "DIS3") (pin "9") (pinfunction "F_9") (pintype "passive"))
      (node (ref "R50") (pin "1") (pinfunction "1_1") (pintype "passive"))
    )
    (net (code "81") (name "Net-(DIS3-G)") (class "Default")
      (node (ref "DIS3") (pin "10") (pinfunction "G_10") (pintype "passive"))
      (node (ref "R51") (pin "1") (pinfunction "1_1") (pintype "passive"))
    )
    (net (code "82") (name "Net-(ENC_1-PadA)") (class "Default")
      (node (ref "ENC_1") (pin "A") (pinfunction "A_A") (pintype "bidirectional"))
      (node (ref "R24") (pin "2") (pinfunction "2_2") (pintype "passive"))
    )
    (net (code "83") (name "Net-(ENC_1-PadB)") (class "Default")
      (node (ref "ENC_1") (pin "B") (pinfunction "B_B") (pintype "bidirectional"))
      (node (ref "R25") (pin "2") (pinfunction "2_2") (pintype "passive"))
    )
    (net (code "84") (name "Net-(ENC_1-PadSW-)") (class "Default")
      (node (ref "ENC_1") (pin "SW-") (pinfunction "SW-_SW-") (pintype "bidirectional"))
      (node (ref "R55") (pin "1") (pinfunction "1_1") (pintype "passive"))
    )
    (net (code "85") (name "Net-(IOE2-IO1_0)") (class "Default")
      (node (ref "D11") (pin "K") (pinfunction "K_K") (pintype "passive"))
      (node (ref "IOE2") (pin "13") (pinfunction "IO1_0_13") (pintype "bidirectional"))
    )
    (net (code "86") (name "Net-(IOE2-IO1_1)") (class "Default")
      (node (ref "D10") (pin "K") (pinfunction "K_K") (pintype "passive"))
      (node (ref "IOE2") (pin "14") (pinfunction "IO1_1_14") (pintype "bidirectional"))
    )
    (net (code "87") (name "Net-(IOE2-IO1_2)") (class "Default")
      (node (ref "D9") (pin "K") (pinfunction "K_K") (pintype "passive"))
      (node (ref "IOE2") (pin "15") (pinfunction "IO1_2_15") (pintype "bidirectional"))
    )
    (net (code "88") (name "Net-(IOE2-IO1_3)") (class "Default")
      (node (ref "D8") (pin "K") (pinfunction "K_K") (pintype "passive"))
      (node (ref "IOE2") (pin "16") (pinfunction "IO1_3_16") (pintype "bidirectional"))
    )
    (net (code "89") (name "Net-(IOE2-IO1_4)") (class "Default")
      (node (ref "D7") (pin "K") (pinfunction "K_K") (pintype "passive"))
      (node (ref "IOE2") (pin "17") (pinfunction "IO1_4_17") (pintype "bidirectional"))
    )
    (net (code "90") (name "Net-(IOE2-IO1_5)") (class "Default")
      (node (ref "D6") (pin "K") (pinfunction "K_K") (pintype "passive"))
      (node (ref "IOE2") (pin "18") (pinfunction "IO1_5_18") (pintype "bidirectional"))
    )
    (net (code "91") (name "Net-(IOE2-IO1_6)") (class "Default")
      (node (ref "D5") (pin "K") (pinfunction "K_K") (pintype "passive"))
      (node (ref "IOE2") (pin "19") (pinfunction "IO1_6_19") (pintype "bidirectional"))
    )
    (net (code "92") (name "Net-(Q1-G)") (class "Default")
      (node (ref "Q1") (pin "1") (pinfunction "G_1") (pintype "passive"))
      (node (ref "R27") (pin "2") (pinfunction "2_2") (pintype "passive"))
    )
    (net (code "93") (name "Net-(R9-Pad2)") (class "Default")
      (node (ref "R9") (pin "2") (pinfunction "2_2") (pintype "passive"))
      (node (ref "SW1") (pin "2") (pinfunction "2_2") (pintype "passive"))
    )
    (net (code "94") (name "Net-(R10-Pad2)") (class "Default")
      (node (ref "R10") (pin "2") (pinfunction "2_2") (pintype "passive"))
      (node (ref "SW2") (pin "2") (pinfunction "2_2") (pintype "passive"))
    )
    (net (code "95") (name "Net-(R11-Pad2)") (class "Default")
      (node (ref "R11") (pin "2") (pinfunction "2_2") (pintype "passive"))
      (node (ref "SW3") (pin "2") (pinfunction "2_2") (pintype "passive"))
    )
    (net (code "96") (name "Net-(R18-Pad2)") (class "Default")
      (node (ref "R18") (pin "2") (pinfunction "2_2") (pintype "passive"))
      (node (ref "SW4") (pin "2") (pinfunction "2_2") (pintype "passive"))
    )
    (net (code "97") (name "Net-(SG1-2)") (class "Default")
      (node (ref "Q1") (pin "2") (pinfunction "D_2") (pintype "passive"))
      (node (ref "Q1") (pin "4") (pinfunction "D_4") (pintype "passive"))
      (node (ref "SG1") (pin "-") (pinfunction "2_-") (pintype "passive"))
    )
    (net (code "98") (name "OSC_IN") (class "Default")
      (node (ref "IC1") (pin "5") (pinfunction "PF0/OSCI_5") (pintype "passive"))
      (node (ref "R53") (pin "1") (pinfunction "1_1") (pintype "passive"))
    )
    (net (code "99") (name "OSC_OUT") (class "Default")
      (node (ref "IC1") (pin "6") (pinfunction "PF1/OSCO_6") (pintype "passive"))
      (node (ref "R54") (pin "1") (pinfunction "1_1") (pintype "passive"))
    )
    (net (code "100") (name "SWCLK") (class "Default")
      (node (ref "CON6") (pin "2") (pinfunction "2_2") (pintype "passive"))
      (node (ref "IC1") (pin "37") (pinfunction "SWC/PA14_37") (pintype "passive"))
      (node (ref "R21") (pin "2") (pinfunction "2_2") (pintype "passive"))
    )
    (net (code "101") (name "SWDIO") (class "Default")
      (node (ref "CON6") (pin "4") (pinfunction "4_4") (pintype "passive"))
      (node (ref "IC1") (pin "34") (pinfunction "SWD/PA13_34") (pintype "passive"))
      (node (ref "R20") (pin "1") (pinfunction "1_1") (pintype "passive"))
    )
    (net (code "102") (name "TH_RES") (class "Default")
      (node (ref "CON1") (pin "5") (pinfunction "5_5") (pintype "passive"))
      (node (ref "IC1") (pin "20") (pinfunction "PB2_20") (pintype "passive"))
    )
    (net (code "103") (name "TRIAC_1") (class "Default")
      (node (ref "CON2") (pin "4") (pinfunction "4_4") (pintype "passive"))
      (node (ref "IC1") (pin "18") (pinfunction "PB0_18") (pintype "passive"))
    )
    (net (code "104") (name "TRIAC_2") (class "Default")
      (node (ref "CON2") (pin "2") (pinfunction "2_2") (pintype "passive"))
      (node (ref "IC1") (pin "19") (pinfunction "PB1_19") (pintype "passive"))
    )
    (net (code "105") (name "TRIAC_3") (class "Default")
      (node (ref "CON2") (pin "1") (pinfunction "1_1") (pintype "passive"))
      (node (ref "IC1") (pin "16") (pinfunction "PA6_16") (pintype "passive"))
    )
    (net (code "106") (name "TRIAC_4") (class "Default")
      (node (ref "CON2") (pin "3") (pinfunction "3_3") (pintype "passive"))
      (node (ref "IC1") (pin "17") (pinfunction "PA7_17") (pintype "passive"))
    )
    (net (code "107") (name "UART_RX") (class "Default")
      (node (ref "CON4") (pin "2") (pinfunction "2_2") (pintype "passive"))
      (node (ref "IC1") (pin "31") (pinfunction "PA10_31") (pintype "passive"))
    )
    (net (code "108") (name "UART_TX") (class "Default")
      (node (ref "CON4") (pin "3") (pinfunction "3_3") (pintype "passive"))
      (node (ref "IC1") (pin "30") (pinfunction "PA9_30") (pintype "passive"))
    )
    (net (code "109") (name "USB_DM") (class "Default")
      (node (ref "CON5") (pin "2") (pinfunction "2_2") (pintype "input"))
      (node (ref "IC1") (pin "32") (pinfunction "PA11_32") (pintype "passive"))
    )
    (net (code "110") (name "USB_DP") (class "Default")
      (node (ref "CON5") (pin "3") (pinfunction "3_3") (pintype "input"))
      (node (ref "IC1") (pin "33") (pinfunction "PA12_33") (pintype "passive"))
    )
    (net (code "111") (name "V+") (class "Default")
      (node (ref "C14") (pin "1") (pinfunction "1_1") (pintype "passive"))
      (node (ref "CON2") (pin "11") (pinfunction "11_11") (pintype "passive"))
      (node (ref "CON2") (pin "13") (pinfunction "13_13") (pintype "passive"))
      (node (ref "D4") (pin "K") (pinfunction "K_K") (pintype "passive"))
      (node (ref "ST1") (pin "1") (pinfunction "IN_1") (pintype "bidirectional"))
    )
    (net (code "112") (name "unconnected-(CON2-Pad8)") (class "Default")
      (node (ref "CON2") (pin "8") (pinfunction "8_8") (pintype "passive"))
    )
    (net (code "113") (name "unconnected-(CON2-Pad10)") (class "Default")
      (node (ref "CON2") (pin "10") (pinfunction "10_10") (pintype "passive"))
    )
    (net (code "114") (name "unconnected-(CON6-Pad6)") (class "Default")
      (node (ref "CON6") (pin "6") (pinfunction "6_6") (pintype "passive"))
    )
    (net (code "115") (name "unconnected-(IC1-PA0-Pad10)") (class "Default")
      (node (ref "IC1") (pin "10") (pinfunction "PA0_10") (pintype "passive"))
    )
    (net (code "116") (name "unconnected-(IC1-PA2-Pad12)") (class "Default")
      (node (ref "IC1") (pin "12") (pinfunction "PA2_12") (pintype "passive"))
    )
    (net (code "117") (name "unconnected-(IC1-PA4-Pad14)") (class "Default")
      (node (ref "IC1") (pin "14") (pinfunction "PA4_14") (pintype "passive"))
    )
    (net (code "118") (name "unconnected-(IC1-PA5-Pad15)") (class "Default")
      (node (ref "IC1") (pin "15") (pinfunction "PA5_15") (pintype "passive"))
    )
    (net (code "119") (name "unconnected-(IC1-PA8-Pad29)") (class "Default")
      (node (ref "IC1") (pin "29") (pinfunction "PA8_29") (pintype "passive"))
    )
    (net (code "120") (name "unconnected-(IC1-PB10-Pad21)") (class "Default")
      (node (ref "IC1") (pin "21") (pinfunction "PB10_21") (pintype "passive"))
    )
    (net (code "121") (name "unconnected-(IC1-PB11-Pad22)") (class "Default")
      (node (ref "IC1") (pin "22") (pinfunction "PB11_22") (pintype "passive"))
    )
    (net (code "122") (name "unconnected-(IC1-PC13-Pad2)") (class "Default")
      (node (ref "IC1") (pin "2") (pinfunction "PC13_2") (pintype "passive"))
    )
    (net (code "123") (name "unconnected-(IC1-PC14{slash}OSC32I-Pad3)") (class "Default")
      (node (ref "IC1") (pin "3") (pinfunction "PC14/OSC32I_3") (pintype "passive"))
    )
    (net (code "124") (name "unconnected-(IC1-PC15{slash}OSC32O-Pad4)") (class "Default")
      (node (ref "IC1") (pin "4") (pinfunction "PC15/OSC32O_4") (pintype "passive"))
    )
    (net (code "125") (name "unconnected-(IOE1-INT-Pad1)") (class "Default")
      (node (ref "IOE1") (pin "1") (pinfunction "INT_1") (pintype "bidirectional"))
    )
    (net (code "126") (name "unconnected-(IOE2-INT-Pad1)") (class "Default")
      (node (ref "IOE2") (pin "1") (pinfunction "INT_1") (pintype "bidirectional"))
    )
    (net (code "127") (name "unconnected-(IOE2-IO1_7-Pad20)") (class "Default")
      (node (ref "IOE2") (pin "20") (pinfunction "IO1_7_20") (pintype "bidirectional"))
    )
    (net (code "128") (name "unconnected-(RESET-Pad3)") (class "Default")
      (node (ref "RESET") (pin "3") (pinfunction "3_3") (pintype "passive"))
    )
    (net (code "129") (name "unconnected-(RESET-Pad4)") (class "Default")
      (node (ref "RESET") (pin "4") (pinfunction "4_4") (pintype "passive"))
    )
    (net (code "130") (name "unconnected-(SW1-Pad3)") (class "Default")
      (node (ref "SW1") (pin "3") (pinfunction "3_3") (pintype "passive"))
    )
    (net (code "131") (name "unconnected-(SW1-Pad4)") (class "Default")
      (node (ref "SW1") (pin "4") (pinfunction "4_4") (pintype "passive"))
    )
    (net (code "132") (name "unconnected-(SW2-Pad3)") (class "Default")
      (node (ref "SW2") (pin "3") (pinfunction "3_3") (pintype "passive"))
    )
    (net (code "133") (name "unconnected-(SW2-Pad4)") (class "Default")
      (node (ref "SW2") (pin "4") (pinfunction "4_4") (pintype "passive"))
    )
    (net (code "134") (name "unconnected-(SW3-Pad3)") (class "Default")
      (node (ref "SW3") (pin "3") (pinfunction "3_3") (pintype "passive"))
    )
    (net (code "135") (name "unconnected-(SW3-Pad4)") (class "Default")
      (node (ref "SW3") (pin "4") (pinfunction "4_4") (pintype "passive"))
    )
    (net (code "136") (name "unconnected-(SW4-Pad3)") (class "Default")
      (node (ref "SW4") (pin "3") (pinfunction "3_3") (pintype "passive"))
    )
    (net (code "137") (name "unconnected-(SW4-Pad4)") (class "Default")
      (node (ref "SW4") (pin "4") (pinfunction "4_4") (pintype "passive"))
    )
  )
)
